# rf24_uno-shield.net
KiCad netlist of a schematic drawn in EAGLE
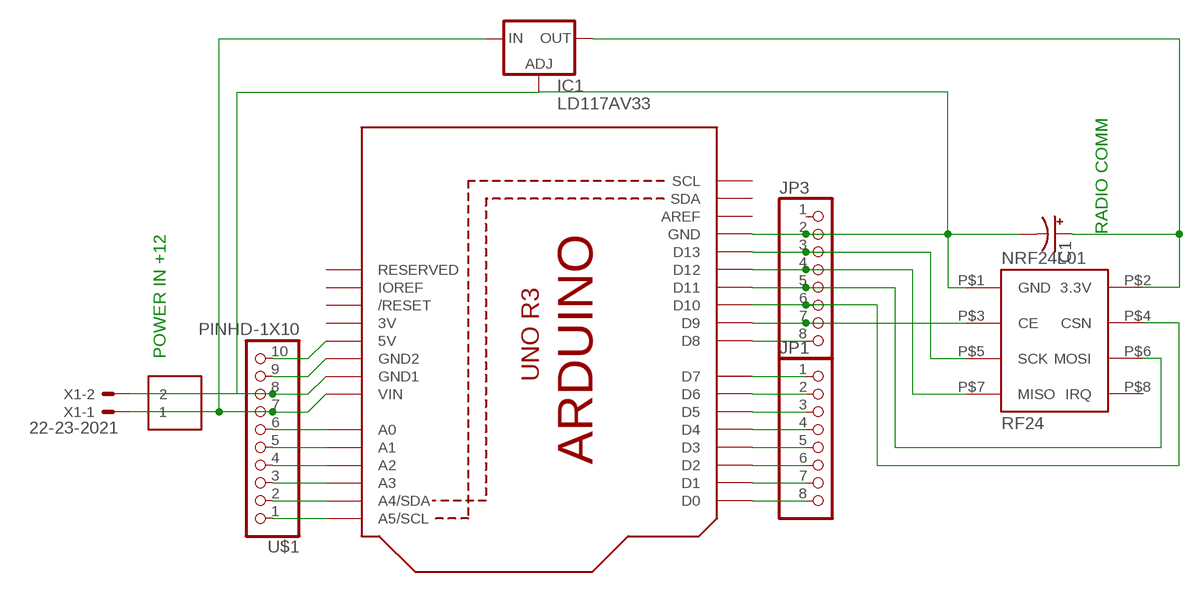
[diagram p0: schematic, sheet 1]

(export (version "E")
  (design (tool "Eeschema 10.0.6"))
  (components
    (comp (ref "+12V")
      (value "1X2-3.5MM")
      (footprint "eagle-import:1X2-3.5MM")
      (libsource (lib "eagle-import") (part "1X2-3.5MM"))
    )
    (comp (ref "C1")
      (value "CPOL-USE2-5")
      (footprint "eagle-import:E2-5")
      (libsource (lib "eagle-import") (part "CPOL-USE2-5"))
    )
    (comp (ref "IC1")
      (value "LD117AV33")
      (footprint "eagle-import:TO220L1")
      (libsource (lib "eagle-import") (part "LD117A?V33"))
    )
    (comp (ref "JP1")
      (value "PINHD-1X8BIG")
      (footprint "eagle-import:1X08-BIG")
      (libsource (lib "eagle-import") (part "PINHD-1X8BIG"))
    )
    (comp (ref "JP3")
      (value "PINHD-1X8BIG")
      (footprint "eagle-import:1X08-BIG")
      (libsource (lib "eagle-import") (part "PINHD-1X8BIG"))
    )
    (comp (ref "NRF24L01")
      (value "RF24")
      (footprint "eagle-import:4X2HEADER")
      (libsource (lib "eagle-import") (part "RF24"))
    )
    (comp (ref "U$1")
      (value "PINHD-1X10")
      (footprint "eagle-import:1X10-BIG")
      (libsource (lib "eagle-import") (part "PINHD-1X10"))
    )
    (comp (ref "U1")
      (value "ARDUINOR3-DIMENSION")
      (footprint "eagle-import:ARDUINOR3")
      (libsource (lib "eagle-import") (part "ARDUINOR3-DIMENSION"))
    )
    (comp (ref "X1")
      (value "22-23-2021")
      (footprint "eagle-import:22-23-2021")
      (fields (field (name "MF") "MOLEX"))
      (libsource (lib "eagle-import") (part "22-23-2021"))
    )
  )
  (nets
    (net (code "1") (name "/3V") (class "Default")
      (node (ref "U1") (pin "3V") (pinfunction "3V_3V") (pintype "power_in"))
    )
    (net (code "2") (name "Net-(IC1-ADJ)") (class "Default")
      (node (ref "+12V") (pin "2") (pinfunction "2_2") (pintype "passive"))
      (node (ref "C1") (pin "-") (pinfunction "-_-") (pintype "passive"))
      (node (ref "IC1") (pin "1") (pinfunction "ADJ_1") (pintype "input"))
      (node (ref "JP3") (pin "2") (pinfunction "2_2") (pintype "passive"))
      (node (ref "NRF24L01") (pin "P$1") (pinfunction "GND_P$1") (pintype "bidirectional"))
      (node (ref "U$1") (pin "8") (pinfunction "8_8") (pintype "passive"))
      (node (ref "U1") (pin "GND") (pinfunction "GND_GND") (pintype "power_in"))
      (node (ref "U1") (pin "GND1") (pinfunction "GND1_GND1") (pintype "power_in"))
      (node (ref "X1") (pin "2") (pinfunction "S_2") (pintype "passive"))
    )
    (net (code "3") (name "Net-(IC1-IN)") (class "Default")
      (node (ref "+12V") (pin "1") (pinfunction "1_1") (pintype "passive"))
      (node (ref "IC1") (pin "3") (pinfunction "IN_3") (pintype "input"))
      (node (ref "U$1") (pin "7") (pinfunction "7_7") (pintype "passive"))
      (node (ref "U1") (pin "VIN") (pinfunction "VIN_VIN") (pintype "power_in"))
      (node (ref "X1") (pin "1") (pinfunction "S_1") (pintype "passive"))
    )
    (net (code "4") (name "Net-(IC1-OUT)") (class "Default")
      (node (ref "C1") (pin "+") (pinfunction "+_+") (pintype "passive"))
      (node (ref "IC1") (pin "2") (pinfunction "OUT_2") (pintype "passive"))
      (node (ref "NRF24L01") (pin "P$2") (pinfunction "3.3V_P$2") (pintype "bidirectional"))
    )
    (net (code "5") (name "Net-(JP1-Pad1)") (class "Default")
      (node (ref "JP1") (pin "1") (pinfunction "1_1") (pintype "passive"))
      (node (ref "U1") (pin "D7") (pinfunction "D7_D7") (pintype "bidirectional"))
    )
    (net (code "6") (name "Net-(JP1-Pad2)") (class "Default")
      (node (ref "JP1") (pin "2") (pinfunction "2_2") (pintype "passive"))
      (node (ref "U1") (pin "D6") (pinfunction "D6_D6") (pintype "bidirectional"))
    )
    (net (code "7") (name "Net-(JP1-Pad3)") (class "Default")
      (node (ref "JP1") (pin "3") (pinfunction "3_3") (pintype "passive"))
      (node (ref "U1") (pin "D5") (pinfunction "D5_D5") (pintype "bidirectional"))
    )
    (net (code "8") (name "Net-(JP1-Pad4)") (class "Default")
      (node (ref "JP1") (pin "4") (pinfunction "4_4") (pintype "passive"))
      (node (ref "U1") (pin "D4") (pinfunction "D4_D4") (pintype "bidirectional"))
    )
    (net (code "9") (name "Net-(JP1-Pad5)") (class "Default")
      (node (ref "JP1") (pin "5") (pinfunction "5_5") (pintype "passive"))
      (node (ref "U1") (pin "D3") (pinfunction "D3_D3") (pintype "bidirectional"))
    )
    (net (code "10") (name "Net-(JP1-Pad6)") (class "Default")
      (node (ref "JP1") (pin "6") (pinfunction "6_6") (pintype "passive"))
      (node (ref "U1") (pin "D2") (pinfunction "D2_D2") (pintype "bidirectional"))
    )
    (net (code "11") (name "Net-(JP1-Pad7)") (class "Default")
      (node (ref "JP1") (pin "7") (pinfunction "7_7") (pintype "passive"))
      (node (ref "U1") (pin "D1") (pinfunction "D1_D1") (pintype "bidirectional"))
    )
    (net (code "12") (name "Net-(JP1-Pad8)") (class "Default")
      (node (ref "JP1") (pin "8") (pinfunction "8_8") (pintype "passive"))
      (node (ref "U1") (pin "D0") (pinfunction "D0_D0") (pintype "bidirectional"))
    )
    (net (code "13") (name "Net-(JP3-Pad8)") (class "Default")
      (node (ref "JP3") (pin "8") (pinfunction "8_8") (pintype "passive"))
      (node (ref "U1") (pin "D8") (pinfunction "D8_D8") (pintype "bidirectional"))
    )
    (net (code "14") (name "Net-(NRF24L01-CE)") (class "Default")
      (node (ref "JP3") (pin "7") (pinfunction "7_7") (pintype "passive"))
      (node (ref "NRF24L01") (pin "P$3") (pinfunction "CE_P$3") (pintype "bidirectional"))
      (node (ref "U1") (pin "D9") (pinfunction "D9_D9") (pintype "bidirectional"))
    )
    (net (code "15") (name "Net-(NRF24L01-CSN)") (class "Default")
      (node (ref "JP3") (pin "6") (pinfunction "6_6") (pintype "passive"))
      (node (ref "NRF24L01") (pin "P$4") (pinfunction "CSN_P$4") (pintype "bidirectional"))
      (node (ref "U1") (pin "D10") (pinfunction "D10_D10") (pintype "bidirectional"))
    )
    (net (code "16") (name "Net-(NRF24L01-MISO)") (class "Default")
      (node (ref "JP3") (pin "4") (pinfunction "4_4") (pintype "passive"))
      (node (ref "NRF24L01") (pin "P$7") (pinfunction "MISO_P$7") (pintype "bidirectional"))
      (node (ref "U1") (pin "D12") (pinfunction "D12_D12") (pintype "bidirectional"))
    )
    (net (code "17") (name "Net-(NRF24L01-MOSI)") (class "Default")
      (node (ref "JP3") (pin "5") (pinfunction "5_5") (pintype "passive"))
      (node (ref "NRF24L01") (pin "P$6") (pinfunction "MOSI_P$6") (pintype "bidirectional"))
      (node (ref "U1") (pin "D11") (pinfunction "D11_D11") (pintype "bidirectional"))
    )
    (net (code "18") (name "Net-(NRF24L01-SCK)") (class "Default")
      (node (ref "JP3") (pin "3") (pinfunction "3_3") (pintype "passive"))
      (node (ref "NRF24L01") (pin "P$5") (pinfunction "SCK_P$5") (pintype "bidirectional"))
      (node (ref "U1") (pin "D13") (pinfunction "D13_D13") (pintype "bidirectional"))
    )
    (net (code "19") (name "Net-(U$1-Pad3)") (class "Default")
      (node (ref "U$1") (pin "3") (pinfunction "3_3") (pintype "passive"))
      (node (ref "U1") (pin "A3") (pinfunction "A3_A3") (pintype "bidirectional"))
    )
    (net (code "20") (name "Net-(U$1-Pad4)") (class "Default")
      (node (ref "U$1") (pin "4") (pinfunction "4_4") (pintype "passive"))
      (node (ref "U1") (pin "A2") (pinfunction "A2_A2") (pintype "bidirectional"))
    )
    (net (code "21") (name "Net-(U$1-Pad5)") (class "Default")
      (node (ref "U$1") (pin "5") (pinfunction "5_5") (pintype "passive"))
      (node (ref "U1") (pin "A1") (pinfunction "A1_A1") (pintype "bidirectional"))
    )
    (net (code "22") (name "Net-(U$1-Pad6)") (class "Default")
      (node (ref "U$1") (pin "6") (pinfunction "6_6") (pintype "passive"))
      (node (ref "U1") (pin "A0") (pinfunction "A0_A0") (pintype "bidirectional"))
    )
    (net (code "23") (name "Net-(U$1-Pad9)") (class "Default")
      (node (ref "U$1") (pin "9") (pinfunction "9_9") (pintype "passive"))
      (node (ref "U1") (pin "GND2") (pinfunction "GND2_GND2") (pintype "power_in"))
    )
    (net (code "24") (name "Net-(U$1-Pad10)") (class "Default")
      (node (ref "U$1") (pin "10") (pinfunction "10_10") (pintype "passive"))
      (node (ref "U1") (pin "5V") (pinfunction "5V_5V") (pintype "power_in"))
    )
    (net (code "25") (name "Net-(U1-A4{slash}SDA)") (class "Default")
      (node (ref "U$1") (pin "2") (pinfunction "2_2") (pintype "passive"))
      (node (ref "U1") (pin "A4") (pinfunction "A4/SDA_A4") (pintype "bidirectional"))
    )
    (net (code "26") (name "Net-(U1-A5{slash}SCL)") (class "Default")
      (node (ref "U$1") (pin "1") (pinfunction "1_1") (pintype "passive"))
      (node (ref "U1") (pin "A5") (pinfunction "A5/SCL_A5") (pintype "bidirectional"))
    )
    (net (code "27") (name "unconnected-(JP3-Pad1)") (class "Default")
      (node (ref "JP3") (pin "1") (pinfunction "1_1") (pintype "passive"))
    )
    (net (code "28") (name "unconnected-(NRF24L01-IRQ-PadP$8)") (class "Default")
      (node (ref "NRF24L01") (pin "P$8") (pinfunction "IRQ_P$8") (pintype "bidirectional"))
    )
    (net (code "29") (name "unconnected-(U1-PadAREF)") (class "Default")
      (node (ref "U1") (pin "AREF") (pinfunction "AREF_AREF") (pintype "bidirectional"))
    )
    (net (code "30") (name "unconnected-(U1-PadIOREF)") (class "Default")
      (node (ref "U1") (pin "IOREF") (pinfunction "IOREF_IOREF") (pintype "output"))
    )
    (net (code "31") (name "unconnected-(U1-PadRESERVED)") (class "Default")
      (node (ref "U1") (pin "RESERVED") (pinfunction "RESERVED_RESERVED") (pintype "no_connect"))
    )
    (net (code "32") (name "unconnected-(U1-PadSCL)") (class "Default")
      (node (ref "U1") (pin "SCL") (pinfunction "SCL_SCL") (pintype "bidirectional"))
    )
    (net (code "33") (name "unconnected-(U1-PadSDA)") (class "Default")
      (node (ref "U1") (pin "SDA") (pinfunction "SDA_SDA") (pintype "bidirectional"))
    )
    (net (code "34") (name "unconnected-(U1-{slash}RESET-PadRESET)") (class "Default")
      (node (ref "U1") (pin "RESET") (pinfunction "/RESET_RESET") (pintype "bidirectional"))
    )
  )
)
